# 5V_Buck_Boost_Converter.net
KiCad netlist of a schematic drawn in Altium Designer
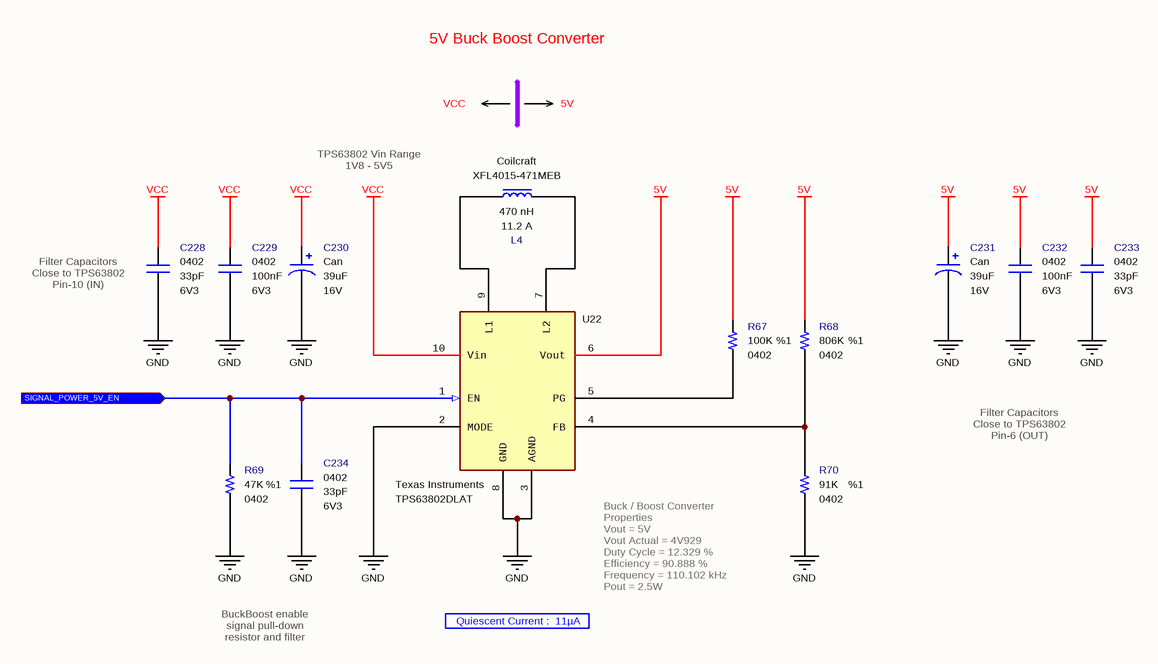
[diagram p0: 5V Buck Boost Converter.SchDoc]

(export (version "E")
  (design (tool "Eeschema 10.0.6"))
  (components
    (comp (ref "C228")
      (value "33pF")
      (footprint "CAPACITOR_0402")
      (description "Capacitor - 33pF [0402] (Ceramic)")
      (fields
        (field (name "TOLERANCE") "10%")
        (field (name "CASE") "0402")
        (field (name "VOLTAGE") "6V3")
        (field (name "MANUFACTURER PART NUMBER") "C0402C330J9RACAUTO")
      )
      (libsource (lib "Ovoo_Library") (part "Capacitor - 33pF [0402-6V3]"))
    )
    (comp (ref "C229")
      (value "100nF")
      (footprint "CAPACITOR_0402")
      (description "Capacitor - 100nF [0402-6V3] (Ceramic)")
      (fields
        (field (name "CASE") "0402")
        (field (name "TOLERANCE") "%10")
        (field (name "VOLTAGE") "6V3")
        (field (name "MANUFACTURER PART NUMBER") "04026D104KAT4A")
      )
      (libsource (lib "Ovoo_Library") (part "Capacitor - 100nF [0402-6V3]"))
    )
    (comp (ref "C230")
      (value "39uF")
      (footprint "CAPACITOR_CAN-B6")
      (description "Capacitor - 39uF 16V [Can] (Electrolytic)")
      (fields
        (field (name "TOLERANCE") "20%")
        (field (name "CASE") "Can")
        (field (name "VOLTAGE") "16V")
        (field (name "MANUFACTURER PART NUMBER") "16SVPC39MV")
      )
      (libsource (lib "Ovoo_Library") (part "Capacitor - 39uF [Can-16V]"))
    )
    (comp (ref "C231")
      (value "39uF")
      (footprint "CAPACITOR_CAN-B6")
      (description "Capacitor - 39uF 16V [Can] (Electrolytic)")
      (fields
        (field (name "TOLERANCE") "20%")
        (field (name "CASE") "Can")
        (field (name "VOLTAGE") "16V")
        (field (name "MANUFACTURER PART NUMBER") "16SVPC39MV")
      )
      (libsource (lib "Ovoo_Library") (part "Capacitor - 39uF [Can-16V]"))
    )
    (comp (ref "C232")
      (value "100nF")
      (footprint "CAPACITOR_0402")
      (description "Capacitor - 100nF [0402-6V3] (Ceramic)")
      (fields
        (field (name "CASE") "0402")
        (field (name "TOLERANCE") "%10")
        (field (name "VOLTAGE") "6V3")
        (field (name "MANUFACTURER PART NUMBER") "04026D104KAT4A")
      )
      (libsource (lib "Ovoo_Library") (part "Capacitor - 100nF [0402-6V3]"))
    )
    (comp (ref "C233")
      (value "33pF")
      (footprint "CAPACITOR_0402")
      (description "Capacitor - 33pF [0402] (Ceramic)")
      (fields
        (field (name "TOLERANCE") "10%")
        (field (name "CASE") "0402")
        (field (name "VOLTAGE") "6V3")
        (field (name "MANUFACTURER PART NUMBER") "C0402C330J9RACAUTO")
      )
      (libsource (lib "Ovoo_Library") (part "Capacitor - 33pF [0402-6V3]"))
    )
    (comp (ref "C234")
      (value "33pF")
      (footprint "CAPACITOR_0402")
      (description "Capacitor - 33pF [0402] (Ceramic)")
      (fields
        (field (name "TOLERANCE") "10%")
        (field (name "CASE") "0402")
        (field (name "VOLTAGE") "6V3")
        (field (name "MANUFACTURER PART NUMBER") "C0402C330J9RACAUTO")
      )
      (libsource (lib "Ovoo_Library") (part "Capacitor - 33pF [0402-6V3]"))
    )
    (comp (ref "L4")
      (value "470 nH")
      (footprint "INDUCTOR_XFL4015")
      (description "Fixed Inductors 0.47uH 20% 11.2A 8.36mOhms AEC-Q200")
      (fields
        (field (name "TOLERANCE") "20%")
        (field (name "MAXIMUM DC CURRENT") "11.2 A")
        (field (name "MANUFACTURER PART NUMBER") "XFL4015-471MEB")
        (field (name "MANUFACTURER NAME") "Coilcraft")
        (field (name "Comment") "Fixed Inductor")
      )
      (libsource (lib "Ovoo_Library") (part "Inductor - 470 nH [SMD]"))
    )
    (comp (ref "R67")
      (value "100K")
      (footprint "RESISTOR_0402")
      (description "Thick Film Resistors - SMD 1/16 W 100 Kohms 1%")
      (fields
        (field (name "TOLERANCE") "%1")
        (field (name "CASE") "0402")
        (field (name "MANUFACTURER PART NUMBER") "CRCW0402100KFKED")
        (field (name "MOUSER PART NUMBER") "71-CRCW0402-100K-E3")
      )
      (libsource (lib "Ovoo_Library") (part "Resistor - 100K"))
    )
    (comp (ref "R68")
      (value "806K")
      (footprint "RESISTOR_0402")
      (description "Thick Film Resistors - SMD 1/16 W 806 Kohms 1%")
      (fields
        (field (name "TOLERANCE") "%1")
        (field (name "CASE") "0402")
        (field (name "MANUFACTURER PART NUMBER") "CRCW0402806KFKED")
        (field (name "MOUSER PART NUMBER") "71-CRCW0402-806K-E3")
      )
      (libsource (lib "Ovoo_Library") (part "Resistor - 806K"))
    )
    (comp (ref "R69")
      (value "47K")
      (footprint "RESISTOR_0402")
      (description "Thick Film Resistors - SMD 1/16 W 47 Kohms 1%")
      (fields
        (field (name "TOLERANCE") "%1")
        (field (name "CASE") "0402")
        (field (name "MANUFACTURER PART NUMBER") "CRCW040247K0FKED")
        (field (name "Comment") "47K - 0402 - %1 - 1/16W")
      )
      (libsource (lib "Ovoo_Library") (part "Resistor - 47K"))
    )
    (comp (ref "R70")
      (value "91K")
      (footprint "RESISTOR_0402")
      (description "Thick Film Resistors - SMD 1/16 W 91 Kohms 1%")
      (fields
        (field (name "TOLERANCE") "%1")
        (field (name "CASE") "0402")
        (field (name "MANUFACTURER PART NUMBER") "CRCW040291K0FKED")
        (field (name "MOUSER PART NUMBER") "71-CRCW040291K0FKED")
      )
      (libsource (lib "Ovoo_Library") (part "Resistor - 91K"))
    )
    (comp (ref "U22")
      (value "Buck-Boost Converter")
      (footprint "VSON-10")
      (fields
        (field (name "MOUSER PART NUMBER") "595-TPS63802DLAT")
        (field (name "MANUFACTURER PART NUMBER") "TPS63802DLAT")
        (field (name "MANUFACTURER NAME") "Texas Instruments")
      )
      (libsource (lib "Ovoo_Library") (part "IC - TPS63802DLAT"))
    )
  )
  (nets
    (net (code "1") (name "/SIGNAL_POWER_5V_EN") (class "Default")
      (node (ref "C234") (pin "2") (pinfunction "2_2") (pintype "passive"))
      (node (ref "R69") (pin "2") (pinfunction "2_2") (pintype "passive"))
      (node (ref "U22") (pin "1") (pinfunction "EN_1") (pintype "input"))
    )
    (net (code "2") (name "5V") (class "Default")
      (node (ref "C231") (pin "1") (pinfunction "1_1") (pintype "passive"))
      (node (ref "C232") (pin "1") (pinfunction "1_1") (pintype "passive"))
      (node (ref "C233") (pin "2") (pinfunction "2_2") (pintype "passive"))
      (node (ref "R67") (pin "2") (pinfunction "2_2") (pintype "passive"))
      (node (ref "R68") (pin "2") (pinfunction "2_2") (pintype "passive"))
      (node (ref "U22") (pin "6") (pinfunction "Vout_6") (pintype "power_in"))
    )
    (net (code "3") (name "GND") (class "Default")
      (node (ref "C228") (pin "1") (pinfunction "1_1") (pintype "passive"))
      (node (ref "C229") (pin "2") (pinfunction "2_2") (pintype "passive"))
      (node (ref "C230") (pin "2") (pinfunction "2_2") (pintype "passive"))
      (node (ref "C231") (pin "2") (pinfunction "2_2") (pintype "passive"))
      (node (ref "C232") (pin "2") (pinfunction "2_2") (pintype "passive"))
      (node (ref "C233") (pin "1") (pinfunction "1_1") (pintype "passive"))
      (node (ref "C234") (pin "1") (pinfunction "1_1") (pintype "passive"))
      (node (ref "R69") (pin "1") (pinfunction "1_1") (pintype "passive"))
      (node (ref "R70") (pin "1") (pinfunction "1_1") (pintype "passive"))
      (node (ref "U22") (pin "2") (pinfunction "MODE_2") (pintype "passive"))
      (node (ref "U22") (pin "3") (pinfunction "AGND_3") (pintype "power_in"))
      (node (ref "U22") (pin "8") (pinfunction "GND_8") (pintype "power_in"))
    )
    (net (code "4") (name "Net-(U22-FB)") (class "Default")
      (node (ref "R68") (pin "1") (pinfunction "1_1") (pintype "passive"))
      (node (ref "R70") (pin "2") (pinfunction "2_2") (pintype "passive"))
      (node (ref "U22") (pin "4") (pinfunction "FB_4") (pintype "passive"))
    )
    (net (code "5") (name "Net-(U22-L1)") (class "Default")
      (node (ref "L4") (pin "1") (pinfunction "1_1") (pintype "passive"))
      (node (ref "U22") (pin "9") (pinfunction "L1_9") (pintype "passive"))
    )
    (net (code "6") (name "Net-(U22-L2)") (class "Default")
      (node (ref "L4") (pin "2") (pinfunction "2_2") (pintype "passive"))
      (node (ref "U22") (pin "7") (pinfunction "L2_7") (pintype "passive"))
    )
    (net (code "7") (name "Net-(U22-PG)") (class "Default")
      (node (ref "R67") (pin "1") (pinfunction "1_1") (pintype "passive"))
      (node (ref "U22") (pin "5") (pinfunction "PG_5") (pintype "passive"))
    )
    (net (code "8") (name "VCC") (class "Default")
      (node (ref "C228") (pin "2") (pinfunction "2_2") (pintype "passive"))
      (node (ref "C229") (pin "1") (pinfunction "1_1") (pintype "passive"))
      (node (ref "C230") (pin "1") (pinfunction "1_1") (pintype "passive"))
      (node (ref "U22") (pin "10") (pinfunction "Vin_10") (pintype "power_in"))
    )
  )
)
